# 3_CAN_CENR-50M_Flow_Relays_LEDs.net
KiCad netlist of a schematic drawn in Altium Designer
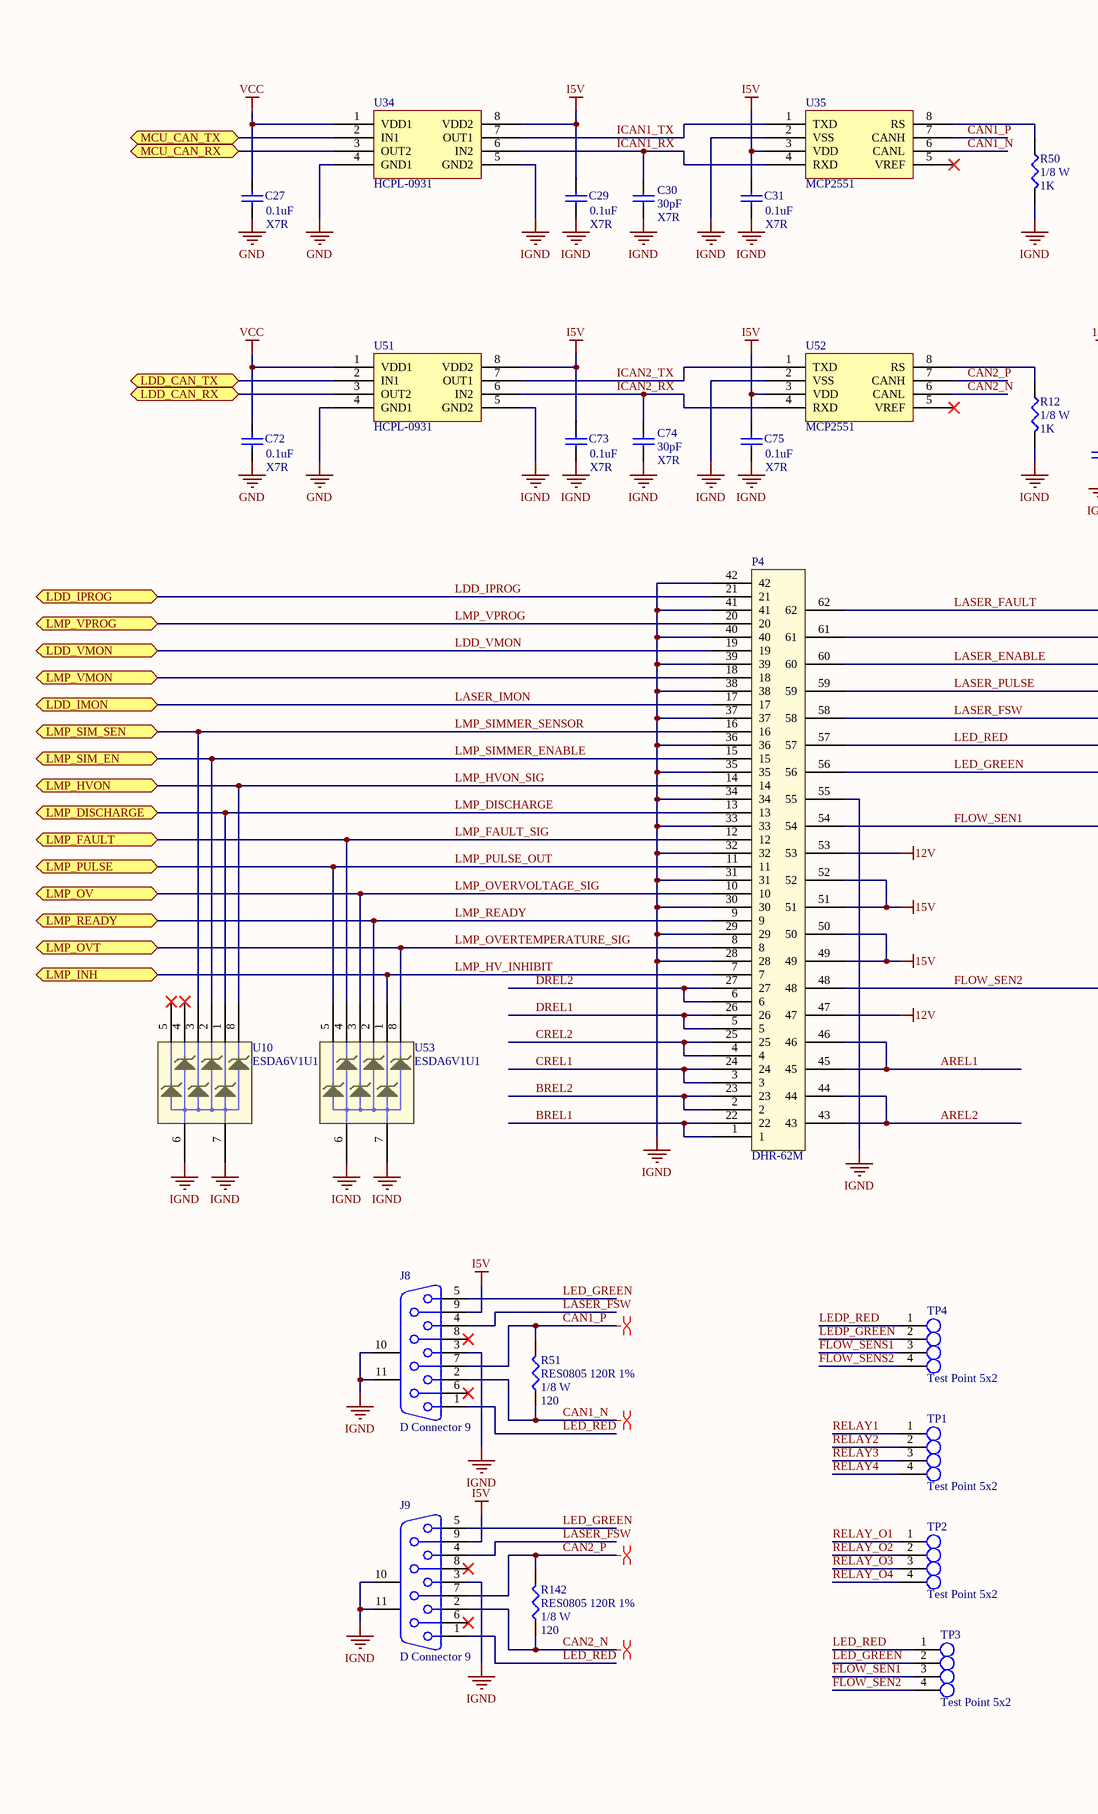
[diagram p0: [3] CAN, CENR-50M, Flow, Relays, LEDs.SchDoc, left]
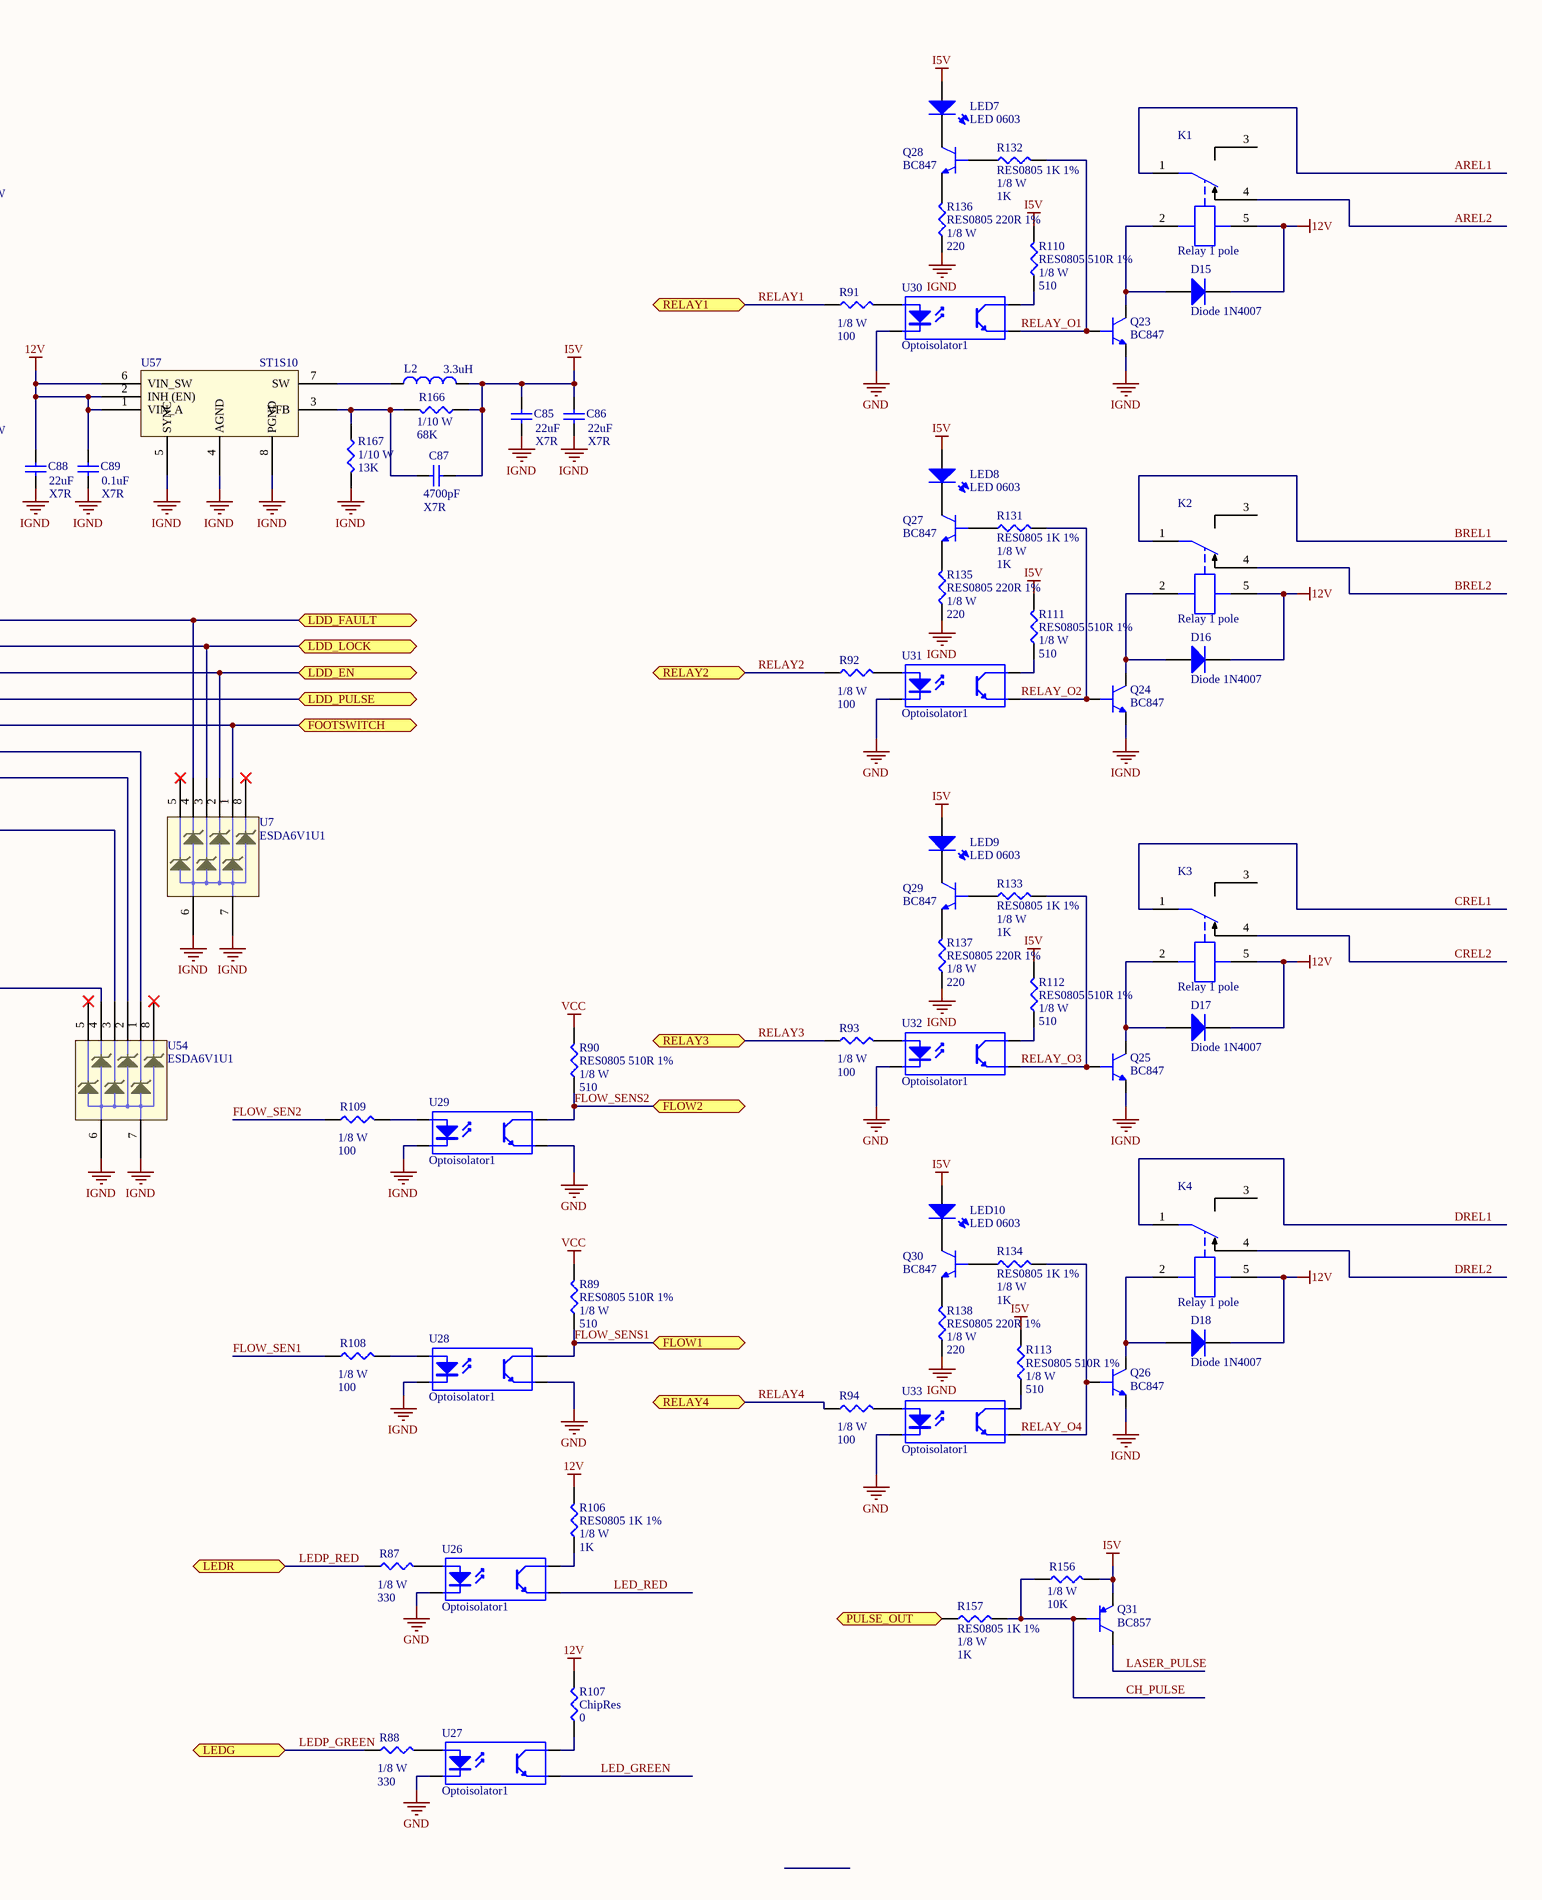
[diagram p1: [3] CAN, CENR-50M, Flow, Relays, LEDs.SchDoc, right]

(export (version "E")
  (design (tool "Eeschema 10.0.6"))
  (components
    (comp (ref "C27")
      (value "0.1uF")
      (footprint "CAP0805")
      (description "Surface-mount ceramic multilayer capacitor")
      (fields (field (name "VOLTAGE") "50V") (field (name "TOLERANCE") "5%") (field (name "TYPE") "X7R"))
      (libsource (lib "Capacitors") (part "CAP0805 0.1uF X7R"))
    )
    (comp (ref "C29")
      (value "0.1uF")
      (footprint "CAP0805")
      (description "Surface-mount ceramic multilayer capacitor")
      (fields (field (name "VOLTAGE") "50V") (field (name "TOLERANCE") "5%") (field (name "TYPE") "X7R"))
      (libsource (lib "Capacitors") (part "CAP0805 0.1uF X7R"))
    )
    (comp (ref "C30")
      (value "30pF")
      (footprint "CAP0805")
      (description "Surface-mount ceramic multilayer capacitor")
      (fields (field (name "VOLTAGE") "50V") (field (name "TOLERANCE") "5%") (field (name "TYPE") "X7R"))
      (libsource (lib "Capacitors") (part "CAP0805 30pF X7R"))
    )
    (comp (ref "C31")
      (value "0.1uF")
      (footprint "CAP0805")
      (description "Surface-mount ceramic multilayer capacitor")
      (fields (field (name "VOLTAGE") "50V") (field (name "TOLERANCE") "5%") (field (name "TYPE") "X7R"))
      (libsource (lib "Capacitors") (part "CAP0805 0.1uF X7R"))
    )
    (comp (ref "C72")
      (value "0.1uF")
      (footprint "CAP0805")
      (description "Surface-mount ceramic multilayer capacitor")
      (fields (field (name "VOLTAGE") "50V") (field (name "TOLERANCE") "5%") (field (name "TYPE") "X7R"))
      (libsource (lib "Capacitors") (part "CAP0805 0.1uF X7R"))
    )
    (comp (ref "C73")
      (value "0.1uF")
      (footprint "CAP0805")
      (description "Surface-mount ceramic multilayer capacitor")
      (fields (field (name "VOLTAGE") "50V") (field (name "TOLERANCE") "5%") (field (name "TYPE") "X7R"))
      (libsource (lib "Capacitors") (part "CAP0805 0.1uF X7R"))
    )
    (comp (ref "C74")
      (value "30pF")
      (footprint "CAP0805")
      (description "Surface-mount ceramic multilayer capacitor")
      (fields (field (name "VOLTAGE") "50V") (field (name "TOLERANCE") "5%") (field (name "TYPE") "X7R"))
      (libsource (lib "Capacitors") (part "CAP0805 30pF X7R"))
    )
    (comp (ref "C75")
      (value "0.1uF")
      (footprint "CAP0805")
      (description "Surface-mount ceramic multilayer capacitor")
      (fields (field (name "VOLTAGE") "50V") (field (name "TOLERANCE") "5%") (field (name "TYPE") "X7R"))
      (libsource (lib "Capacitors") (part "CAP0805 0.1uF X7R"))
    )
    (comp (ref "C85")
      (value "22uF")
      (footprint "CAP1210")
      (description "Surface-mount ceramic multilayer capacitor")
      (fields (field (name "VOLTAGE") "25V") (field (name "TOLERANCE") "10%") (field (name "TYPE") "X7R"))
      (libsource (lib "Capacitors") (part "ChipCap 22uF X7R"))
    )
    (comp (ref "C86")
      (value "22uF")
      (footprint "CAP1210")
      (description "Surface-mount ceramic multilayer capacitor")
      (fields (field (name "VOLTAGE") "25V") (field (name "TOLERANCE") "10%") (field (name "TYPE") "X7R"))
      (libsource (lib "Capacitors") (part "ChipCap 22uF X7R"))
    )
    (comp (ref "C87")
      (value "4700pF")
      (footprint "CAP0603")
      (description "Surface-mount ceramic multilayer capacitor")
      (fields (field (name "VOLTAGE") "16V") (field (name "TOLERANCE") "10%") (field (name "TYPE") "X7R"))
      (libsource (lib "Capacitors") (part "ChipCap 4700 X7R"))
    )
    (comp (ref "C88")
      (value "22uF")
      (footprint "CAP1210")
      (description "Surface-mount ceramic multilayer capacitor")
      (fields (field (name "VOLTAGE") "25V") (field (name "TOLERANCE") "10%") (field (name "TYPE") "X7R"))
      (libsource (lib "Capacitors") (part "ChipCap 22uF X7R"))
    )
    (comp (ref "C89")
      (value "0.1uF")
      (footprint "CAP0603")
      (description "Surface-mount ceramic multilayer capacitor")
      (fields (field (name "VOLTAGE") "100V") (field (name "TOLERANCE") "10%") (field (name "TYPE") "X7R"))
      (libsource (lib "Capacitors") (part "ChipCap 0.1uF X7R"))
    )
    (comp (ref "D15")
      (value "Diode 1N4007")
      (footprint "DO-41")
      (description "1 Amp General Purpose Rectifier")
      (fields (field (name "MANUFACTURER PART NUMBER") "1N4007") (field (name "PUBLISHER") "Altium Limited"))
      (libsource (lib "Miscellaneous Devices") (part "Diode 1N4007"))
    )
    (comp (ref "D16")
      (value "Diode 1N4007")
      (footprint "DO-41")
      (description "1 Amp General Purpose Rectifier")
      (fields (field (name "MANUFACTURER PART NUMBER") "1N4007") (field (name "PUBLISHER") "Altium Limited"))
      (libsource (lib "Miscellaneous Devices") (part "Diode 1N4007"))
    )
    (comp (ref "D17")
      (value "Diode 1N4007")
      (footprint "DO-41")
      (description "1 Amp General Purpose Rectifier")
      (fields (field (name "MANUFACTURER PART NUMBER") "1N4007") (field (name "PUBLISHER") "Altium Limited"))
      (libsource (lib "Miscellaneous Devices") (part "Diode 1N4007"))
    )
    (comp (ref "D18")
      (value "Diode 1N4007")
      (footprint "DO-41")
      (description "1 Amp General Purpose Rectifier")
      (fields (field (name "MANUFACTURER PART NUMBER") "1N4007") (field (name "PUBLISHER") "Altium Limited"))
      (libsource (lib "Miscellaneous Devices") (part "Diode 1N4007"))
    )
    (comp (ref "J8")
      (value "D Connector 9")
      (footprint "DSUB1.385-2H9F")
      (description "Receptacle Assembly, 9 Position, Right Angle")
      (fields
        (field (name "MANUFACTURER PART NUMBER") "DRB-9FA")
        (field (name "MANUFACTURER") "CONNFLY")
        (field (name "PUBLISHER") "Altium Limited")
      )
      (libsource (lib "Connectors") (part "D Connector 9"))
    )
    (comp (ref "J9")
      (value "D Connector 9")
      (footprint "DSUB1.385-2H9F")
      (description "Receptacle Assembly, 9 Position, Right Angle")
      (fields
        (field (name "MANUFACTURER PART NUMBER") "DRB-9FA")
        (field (name "MANUFACTURER") "CONNFLY")
        (field (name "PUBLISHER") "Altium Limited")
      )
      (libsource (lib "Connectors") (part "D Connector 9"))
    )
    (comp (ref "K1")
      (value "Relay 1 pole")
      (footprint "G5LA")
      (description "Relay G5LE 10A Single Pole")
      (libsource (lib "OMRON Relay") (part "Relay G5LE"))
    )
    (comp (ref "K2")
      (value "Relay 1 pole")
      (footprint "G5LA")
      (description "Relay G5LE 10A Single Pole")
      (libsource (lib "OMRON Relay") (part "Relay G5LE"))
    )
    (comp (ref "K3")
      (value "Relay 1 pole")
      (footprint "G5LA")
      (description "Relay G5LE 10A Single Pole")
      (libsource (lib "OMRON Relay") (part "Relay G5LE"))
    )
    (comp (ref "K4")
      (value "Relay 1 pole")
      (footprint "G5LA")
      (description "Relay G5LE 10A Single Pole")
      (libsource (lib "OMRON Relay") (part "Relay G5LE"))
    )
    (comp (ref "L2")
      (value "3.3uH")
      (footprint "SDR0403")
      (description "Inductance")
      (libsource (lib "Common Devices") (part "ChipInductance"))
    )
    (comp (ref "LED7") (value "LED 0603") (footprint "LED 0603") (libsource (lib "LEDs") (part "LED0603")))
    (comp (ref "LED8") (value "LED 0603") (footprint "LED 0603") (libsource (lib "LEDs") (part "LED0603")))
    (comp (ref "LED9") (value "LED 0603") (footprint "LED 0603") (libsource (lib "LEDs") (part "LED0603")))
    (comp (ref "LED10") (value "LED 0603") (footprint "LED 0603") (libsource (lib "LEDs") (part "LED0603")))
    (comp (ref "P4")
      (value "DHR-62M")
      (footprint "DHR-62M")
      (description "Dsub 62 Mail")
      (fields
        (field (name "MANUFACTURER PART NUMBER") "DS1038-62MBNSIA74")
        (field (name "MANUFACTURER") "CONNFLY")
      )
      (libsource (lib "Connectors") (part "DHR-62M"))
    )
    (comp (ref "Q23")
      (value "BC847")
      (footprint "SOT23")
      (description "NPN transistor")
      (fields (field (name "MANUFACTURER") "ONS") (field (name "MANUFACTURER PART NUMBER") "BC847BLT1G"))
      (libsource (lib "BJT") (part "BC847"))
    )
    (comp (ref "Q24")
      (value "BC847")
      (footprint "SOT23")
      (description "NPN transistor")
      (fields (field (name "MANUFACTURER") "ONS") (field (name "MANUFACTURER PART NUMBER") "BC847BLT1G"))
      (libsource (lib "BJT") (part "BC847"))
    )
    (comp (ref "Q25")
      (value "BC847")
      (footprint "SOT23")
      (description "NPN transistor")
      (fields (field (name "MANUFACTURER") "ONS") (field (name "MANUFACTURER PART NUMBER") "BC847BLT1G"))
      (libsource (lib "BJT") (part "BC847"))
    )
    (comp (ref "Q26")
      (value "BC847")
      (footprint "SOT23")
      (description "NPN transistor")
      (fields (field (name "MANUFACTURER") "ONS") (field (name "MANUFACTURER PART NUMBER") "BC847BLT1G"))
      (libsource (lib "BJT") (part "BC847"))
    )
    (comp (ref "Q27")
      (value "BC847")
      (footprint "SOT23")
      (description "NPN transistor")
      (fields (field (name "MANUFACTURER") "ONS") (field (name "MANUFACTURER PART NUMBER") "BC847BLT1G"))
      (libsource (lib "BJT") (part "BC847"))
    )
    (comp (ref "Q28")
      (value "BC847")
      (footprint "SOT23")
      (description "NPN transistor")
      (fields (field (name "MANUFACTURER") "ONS") (field (name "MANUFACTURER PART NUMBER") "BC847BLT1G"))
      (libsource (lib "BJT") (part "BC847"))
    )
    (comp (ref "Q29")
      (value "BC847")
      (footprint "SOT23")
      (description "NPN transistor")
      (fields (field (name "MANUFACTURER") "ONS") (field (name "MANUFACTURER PART NUMBER") "BC847BLT1G"))
      (libsource (lib "BJT") (part "BC847"))
    )
    (comp (ref "Q30")
      (value "BC847")
      (footprint "SOT23")
      (description "NPN transistor")
      (fields (field (name "MANUFACTURER") "ONS") (field (name "MANUFACTURER PART NUMBER") "BC847BLT1G"))
      (libsource (lib "BJT") (part "BC847"))
    )
    (comp (ref "Q31")
      (value "BC857")
      (footprint "SOT23")
      (description "PNP Transistor")
      (fields (field (name "MANUFACTURER") "NXP") (field (name "MANUFACTURER PART NUMBER") "BC857A.215"))
      (libsource (lib "BJT") (part "BC857"))
    )
    (comp (ref "R12")
      (value "1K")
      (footprint "RES0805")
      (description "Think Film Chip resistor")
      (fields
        (field (name "TOLERANCE") "1%")
        (field (name "MANUFACTURER PART NUMBER") "RC0805FR-071KL")
        (field (name "RATING") "1/8 W")
      )
      (libsource (lib "Resistors") (part "RES0805 1K 1%"))
    )
    (comp (ref "R50")
      (value "1K")
      (footprint "RES0805")
      (description "Think Film Chip resistor")
      (fields
        (field (name "TOLERANCE") "1%")
        (field (name "MANUFACTURER PART NUMBER") "RC0805FR-071KL")
        (field (name "RATING") "1/8 W")
      )
      (libsource (lib "Resistors") (part "RES0805 1K 1%"))
    )
    (comp (ref "R51")
      (value "RES0805 120R 1%")
      (footprint "RES0805")
      (description "Think Film Chip resistor")
      (fields
        (field (name "TOLERANCE") "1%")
        (field (name "MANUFACTURER PART NUMBER") "RC0805FR-07120RL")
        (field (name "RATING") "1/8 W")
        (field (name "ALTIUM_VALUE") "120")
      )
      (libsource (lib "Resistors") (part "RES0805 120R 1%"))
    )
    (comp (ref "R87")
      (value "330")
      (footprint "RES0805")
      (description "Think Film Chip resistor")
      (fields
        (field (name "TOLERANCE") "1%")
        (field (name "MANUFACTURER PART NUMBER") "RC0805FR-07330RL")
        (field (name "RATING") "1/8 W")
      )
      (libsource (lib "Resistors") (part "RES0805 330R 1%"))
    )
    (comp (ref "R88")
      (value "330")
      (footprint "RES0805")
      (description "Think Film Chip resistor")
      (fields
        (field (name "TOLERANCE") "1%")
        (field (name "MANUFACTURER PART NUMBER") "RC0805FR-07330RL")
        (field (name "RATING") "1/8 W")
      )
      (libsource (lib "Resistors") (part "RES0805 330R 1%"))
    )
    (comp (ref "R89")
      (value "RES0805 510R 1%")
      (footprint "RES0805")
      (description "Think Film Chip resistor")
      (fields
        (field (name "TOLERANCE") "1%")
        (field (name "MANUFACTURER PART NUMBER") "RC0805FR-07510RL")
        (field (name "RATING") "1/8 W")
        (field (name "ALTIUM_VALUE") "510")
      )
      (libsource (lib "Resistors") (part "RES0805 510R 1%"))
    )
    (comp (ref "R90")
      (value "RES0805 510R 1%")
      (footprint "RES0805")
      (description "Think Film Chip resistor")
      (fields
        (field (name "TOLERANCE") "1%")
        (field (name "MANUFACTURER PART NUMBER") "RC0805FR-07510RL")
        (field (name "RATING") "1/8 W")
        (field (name "ALTIUM_VALUE") "510")
      )
      (libsource (lib "Resistors") (part "RES0805 510R 1%"))
    )
    (comp (ref "R91")
      (value "100")
      (footprint "RES0805")
      (description "Think Film Chip resistor")
      (fields
        (field (name "TOLERANCE") "1%")
        (field (name "MANUFACTURER PART NUMBER") "RC0805FR-07100RL")
        (field (name "RATING") "1/8 W")
      )
      (libsource (lib "Resistors") (part "RES0805 100R 1%"))
    )
    (comp (ref "R92")
      (value "100")
      (footprint "RES0805")
      (description "Think Film Chip resistor")
      (fields
        (field (name "TOLERANCE") "1%")
        (field (name "MANUFACTURER PART NUMBER") "RC0805FR-07100RL")
        (field (name "RATING") "1/8 W")
      )
      (libsource (lib "Resistors") (part "RES0805 100R 1%"))
    )
    (comp (ref "R93")
      (value "100")
      (footprint "RES0805")
      (description "Think Film Chip resistor")
      (fields
        (field (name "TOLERANCE") "1%")
        (field (name "MANUFACTURER PART NUMBER") "RC0805FR-07100RL")
        (field (name "RATING") "1/8 W")
      )
      (libsource (lib "Resistors") (part "RES0805 100R 1%"))
    )
    (comp (ref "R94")
      (value "100")
      (footprint "RES0805")
      (description "Think Film Chip resistor")
      (fields
        (field (name "TOLERANCE") "1%")
        (field (name "MANUFACTURER PART NUMBER") "RC0805FR-07100RL")
        (field (name "RATING") "1/8 W")
      )
      (libsource (lib "Resistors") (part "RES0805 100R 1%"))
    )
    (comp (ref "R106")
      (value "RES0805 1K 1%")
      (footprint "RES0805")
      (description "Think Film Chip resistor")
      (fields
        (field (name "TOLERANCE") "1%")
        (field (name "MANUFACTURER PART NUMBER") "RC0805FR-071KL")
        (field (name "RATING") "1/8 W")
        (field (name "ALTIUM_VALUE") "1K")
      )
      (libsource (lib "Resistors") (part "RES0805 1K 1%"))
    )
    (comp (ref "R107")
      (value "ChipRes")
      (footprint "RES0805")
      (description "Chip resistor")
      (fields (field (name "ALTIUM_VALUE") "0"))
      (libsource (lib "Common Devices") (part "ChipRes"))
    )
    (comp (ref "R108")
      (value "100")
      (footprint "RES0805")
      (description "Think Film Chip resistor")
      (fields
        (field (name "TOLERANCE") "1%")
        (field (name "MANUFACTURER PART NUMBER") "RC0805FR-07100RL")
        (field (name "RATING") "1/8 W")
      )
      (libsource (lib "Resistors") (part "RES0805 100R 1%"))
    )
    (comp (ref "R109")
      (value "100")
      (footprint "RES0805")
      (description "Think Film Chip resistor")
      (fields
        (field (name "TOLERANCE") "1%")
        (field (name "MANUFACTURER PART NUMBER") "RC0805FR-07100RL")
        (field (name "RATING") "1/8 W")
      )
      (libsource (lib "Resistors") (part "RES0805 100R 1%"))
    )
    (comp (ref "R110")
      (value "RES0805 510R 1%")
      (footprint "RES0805")
      (description "Think Film Chip resistor")
      (fields
        (field (name "TOLERANCE") "1%")
        (field (name "MANUFACTURER PART NUMBER") "RC0805FR-07510RL")
        (field (name "RATING") "1/8 W")
        (field (name "ALTIUM_VALUE") "510")
      )
      (libsource (lib "Resistors") (part "RES0805 510R 1%"))
    )
    (comp (ref "R111")
      (value "RES0805 510R 1%")
      (footprint "RES0805")
      (description "Think Film Chip resistor")
      (fields
        (field (name "TOLERANCE") "1%")
        (field (name "MANUFACTURER PART NUMBER") "RC0805FR-07510RL")
        (field (name "RATING") "1/8 W")
        (field (name "ALTIUM_VALUE") "510")
      )
      (libsource (lib "Resistors") (part "RES0805 510R 1%"))
    )
    (comp (ref "R112")
      (value "RES0805 510R 1%")
      (footprint "RES0805")
      (description "Think Film Chip resistor")
      (fields
        (field (name "TOLERANCE") "1%")
        (field (name "MANUFACTURER PART NUMBER") "RC0805FR-07510RL")
        (field (name "RATING") "1/8 W")
        (field (name "ALTIUM_VALUE") "510")
      )
      (libsource (lib "Resistors") (part "RES0805 510R 1%"))
    )
    (comp (ref "R113")
      (value "RES0805 510R 1%")
      (footprint "RES0805")
      (description "Think Film Chip resistor")
      (fields
        (field (name "TOLERANCE") "1%")
        (field (name "MANUFACTURER PART NUMBER") "RC0805FR-07510RL")
        (field (name "RATING") "1/8 W")
        (field (name "ALTIUM_VALUE") "510")
      )
      (libsource (lib "Resistors") (part "RES0805 510R 1%"))
    )
    (comp (ref "R131")
      (value "RES0805 1K 1%")
      (footprint "RES0805")
      (description "Think Film Chip resistor")
      (fields
        (field (name "TOLERANCE") "1%")
        (field (name "MANUFACTURER PART NUMBER") "RC0805FR-071KL")
        (field (name "RATING") "1/8 W")
        (field (name "ALTIUM_VALUE") "1K")
      )
      (libsource (lib "Resistors") (part "RES0805 1K 1%"))
    )
    (comp (ref "R132")
      (value "RES0805 1K 1%")
      (footprint "RES0805")
      (description "Think Film Chip resistor")
      (fields
        (field (name "TOLERANCE") "1%")
        (field (name "MANUFACTURER PART NUMBER") "RC0805FR-071KL")
        (field (name "RATING") "1/8 W")
        (field (name "ALTIUM_VALUE") "1K")
      )
      (libsource (lib "Resistors") (part "RES0805 1K 1%"))
    )
    (comp (ref "R133")
      (value "RES0805 1K 1%")
      (footprint "RES0805")
      (description "Think Film Chip resistor")
      (fields
        (field (name "TOLERANCE") "1%")
        (field (name "MANUFACTURER PART NUMBER") "RC0805FR-071KL")
        (field (name "RATING") "1/8 W")
        (field (name "ALTIUM_VALUE") "1K")
      )
      (libsource (lib "Resistors") (part "RES0805 1K 1%"))
    )
    (comp (ref "R134")
      (value "RES0805 1K 1%")
      (footprint "RES0805")
      (description "Think Film Chip resistor")
      (fields
        (field (name "TOLERANCE") "1%")
        (field (name "MANUFACTURER PART NUMBER") "RC0805FR-071KL")
        (field (name "RATING") "1/8 W")
        (field (name "ALTIUM_VALUE") "1K")
      )
      (libsource (lib "Resistors") (part "RES0805 1K 1%"))
    )
    (comp (ref "R135")
      (value "RES0805 220R 1%")
      (footprint "RES0805")
      (description "Think Film Chip resistor")
      (fields
        (field (name "TOLERANCE") "1%")
        (field (name "MANUFACTURER PART NUMBER") "RC0805JR-07220R")
        (field (name "RATING") "1/8 W")
        (field (name "ALTIUM_VALUE") "220")
      )
      (libsource (lib "Resistors") (part "RES0805 220R 1%"))
    )
    (comp (ref "R136")
      (value "RES0805 220R 1%")
      (footprint "RES0805")
      (description "Think Film Chip resistor")
      (fields
        (field (name "TOLERANCE") "1%")
        (field (name "MANUFACTURER PART NUMBER") "RC0805JR-07220R")
        (field (name "RATING") "1/8 W")
        (field (name "ALTIUM_VALUE") "220")
      )
      (libsource (lib "Resistors") (part "RES0805 220R 1%"))
    )
    (comp (ref "R137")
      (value "RES0805 220R 1%")
      (footprint "RES0805")
      (description "Think Film Chip resistor")
      (fields
        (field (name "TOLERANCE") "1%")
        (field (name "MANUFACTURER PART NUMBER") "RC0805JR-07220R")
        (field (name "RATING") "1/8 W")
        (field (name "ALTIUM_VALUE") "220")
      )
      (libsource (lib "Resistors") (part "RES0805 220R 1%"))
    )
    (comp (ref "R138")
      (value "RES0805 220R 1%")
      (footprint "RES0805")
      (description "Think Film Chip resistor")
      (fields
        (field (name "TOLERANCE") "1%")
        (field (name "MANUFACTURER PART NUMBER") "RC0805JR-07220R")
        (field (name "RATING") "1/8 W")
        (field (name "ALTIUM_VALUE") "220")
      )
      (libsource (lib "Resistors") (part "RES0805 220R 1%"))
    )
    (comp (ref "R142")
      (value "RES0805 120R 1%")
      (footprint "RES0805")
      (description "Think Film Chip resistor")
      (fields
        (field (name "TOLERANCE") "1%")
        (field (name "MANUFACTURER PART NUMBER") "RC0805FR-07120RL")
        (field (name "RATING") "1/8 W")
        (field (name "ALTIUM_VALUE") "120")
      )
      (libsource (lib "Resistors") (part "RES0805 120R 1%"))
    )
    (comp (ref "R156")
      (value "10K")
      (footprint "RES0805")
      (description "Think Film Chip resistor")
      (fields
        (field (name "TOLERANCE") "1%")
        (field (name "MANUFACTURER PART NUMBER") "RC0805FR-0710KL")
        (field (name "RATING") "1/8 W")
      )
      (libsource (lib "Resistors") (part "RES0805 10K 1%"))
    )
    (comp (ref "R157")
      (value "RES0805 1K 1%")
      (footprint "RES0805")
      (description "Think Film Chip resistor")
      (fields
        (field (name "TOLERANCE") "1%")
        (field (name "MANUFACTURER PART NUMBER") "RC0805FR-071KL")
        (field (name "RATING") "1/8 W")
        (field (name "ALTIUM_VALUE") "1K")
      )
      (libsource (lib "Resistors") (part "RES0805 1K 1%"))
    )
    (comp (ref "R166")
      (value "68K")
      (footprint "RES0603")
      (description "Think Film Chip resistor")
      (fields
        (field (name "TOLERANCE") "1%")
        (field (name "RATING") "1/10 W")
        (field (name "Comment") "ChipRes 68K 1%")
      )
      (libsource (lib "Resistors") (part "ChipRes 1K5 1%"))
    )
    (comp (ref "R167")
      (value "13K")
      (footprint "RES0603")
      (description "Think Film Chip resistor")
      (fields
        (field (name "TOLERANCE") "1%")
        (field (name "RATING") "1/10 W")
        (field (name "Comment") "ChipRes 13K 1%")
      )
      (libsource (lib "Resistors") (part "ChipRes 1K5 1%"))
    )
    (comp (ref "TP1")
      (value "Test Point 5x2")
      (footprint "PG-1.5-13.5-4P-2.54PH")
      (libsource (lib "Connectors") (part "PG-1.5-13.5-4P-2.54PH"))
    )
    (comp (ref "TP2")
      (value "Test Point 5x2")
      (footprint "PG-1.5-13.5-4P-2.54PH")
      (libsource (lib "Connectors") (part "PG-1.5-13.5-4P-2.54PH"))
    )
    (comp (ref "TP3")
      (value "Test Point 5x2")
      (footprint "PG-1.5-13.5-4P-2.54PH")
      (libsource (lib "Connectors") (part "PG-1.5-13.5-4P-2.54PH"))
    )
    (comp (ref "TP4")
      (value "Test Point 5x2")
      (footprint "PG-1.5-13.5-4P-2.54PH")
      (libsource (lib "Connectors") (part "PG-1.5-13.5-4P-2.54PH"))
    )
    (comp (ref "U7")
      (value "ESDA6V1U1")
      (footprint "Protection:SOP8")
      (description "Transil Array for ESD protection")
      (libsource (lib "Protection") (part "ESDA6V1U1"))
    )
    (comp (ref "U10")
      (value "ESDA6V1U1")
      (footprint "Protection:SOP8")
      (description "Transil Array for ESD protection")
      (libsource (lib "Protection") (part "ESDA6V1U1"))
    )
    (comp (ref "U26")
      (value "Optoisolator1")
      (footprint "DIP-4")
      (description "4-Pin Phototransistor Optocoupler")
      (fields (field (name "PUBLISHER") "Altium Limited"))
      (libsource (lib "Miscellaneous Devices") (part "Optoisolator1"))
    )
    (comp (ref "U27")
      (value "Optoisolator1")
      (footprint "DIP-4")
      (description "4-Pin Phototransistor Optocoupler")
      (fields (field (name "PUBLISHER") "Altium Limited"))
      (libsource (lib "Miscellaneous Devices") (part "Optoisolator1"))
    )
    (comp (ref "U28")
      (value "Optoisolator1")
      (footprint "DIP-4")
      (description "4-Pin Phototransistor Optocoupler")
      (fields (field (name "PUBLISHER") "Altium Limited"))
      (libsource (lib "Miscellaneous Devices") (part "Optoisolator1"))
    )
    (comp (ref "U29")
      (value "Optoisolator1")
      (footprint "DIP-4")
      (description "4-Pin Phototransistor Optocoupler")
      (fields (field (name "PUBLISHER") "Altium Limited"))
      (libsource (lib "Miscellaneous Devices") (part "Optoisolator1"))
    )
    (comp (ref "U30")
      (value "Optoisolator1")
      (footprint "DIP-4")
      (description "4-Pin Phototransistor Optocoupler")
      (fields (field (name "PUBLISHER") "Altium Limited"))
      (libsource (lib "Miscellaneous Devices") (part "Optoisolator1"))
    )
    (comp (ref "U31")
      (value "Optoisolator1")
      (footprint "DIP-4")
      (description "4-Pin Phototransistor Optocoupler")
      (fields (field (name "PUBLISHER") "Altium Limited"))
      (libsource (lib "Miscellaneous Devices") (part "Optoisolator1"))
    )
    (comp (ref "U32")
      (value "Optoisolator1")
      (footprint "DIP-4")
      (description "4-Pin Phototransistor Optocoupler")
      (fields (field (name "PUBLISHER") "Altium Limited"))
      (libsource (lib "Miscellaneous Devices") (part "Optoisolator1"))
    )
    (comp (ref "U33")
      (value "Optoisolator1")
      (footprint "DIP-4")
      (description "4-Pin Phototransistor Optocoupler")
      (fields (field (name "PUBLISHER") "Altium Limited"))
      (libsource (lib "Miscellaneous Devices") (part "Optoisolator1"))
    )
    (comp (ref "U34")
      (value "HCPL-0931")
      (footprint "SOIC8")
      (description "2-bit bi-direction optoisolated buffer")
      (libsource (lib "AVAGO bi-direction optoisolated buffer") (part "HCPL-0931-000E"))
    )
    (comp (ref "U35")
      (value "MCP2551")
      (footprint "SOIC8")
      (description "CAN Transceiver")
      (libsource (lib "Microchip CAN Transceiver") (part "MCP2551-I/SN"))
    )
    (comp (ref "U51")
      (value "HCPL-0931")
      (footprint "SOIC8")
      (description "2-bit bi-direction optoisolated buffer")
      (libsource (lib "AVAGO bi-direction optoisolated buffer") (part "HCPL-0931-000E"))
    )
    (comp (ref "U52")
      (value "MCP2551")
      (footprint "SOIC8")
      (description "CAN Transceiver")
      (libsource (lib "Microchip CAN Transceiver") (part "MCP2551-I/SN"))
    )
    (comp (ref "U53")
      (value "ESDA6V1U1")
      (footprint "Protection:SOP8")
      (description "Transil Array for ESD protection")
      (libsource (lib "Protection") (part "ESDA6V1U1"))
    )
    (comp (ref "U54")
      (value "ESDA6V1U1")
      (footprint "Protection:SOP8")
      (description "Transil Array for ESD protection")
      (libsource (lib "Protection") (part "ESDA6V1U1"))
    )
    (comp (ref "U57")
      (value "ST1S10")
      (footprint "SOIC8")
      (description "3 A, 900 kHz, monolithic synchronous step-down regulator IC")
      (fields (field (name "MANUFACTURER") "ST"))
      (libsource (lib "ST DC-DC") (part "ST1S10"))
    )
  )
  (nets
    (net (code "1") (name "/AREL1") (class "Default")
      (node (ref "K1") (pin "1") (pinfunction "1_1") (pintype "passive"))
      (node (ref "P4") (pin "45") (pinfunction "45_45") (pintype "passive"))
      (node (ref "P4") (pin "46") (pinfunction "46_46") (pintype "passive"))
    )
    (net (code "2") (name "/AREL2") (class "Default")
      (node (ref "K1") (pin "4") (pinfunction "4_4") (pintype "passive"))
      (node (ref "P4") (pin "43") (pinfunction "43_43") (pintype "passive"))
      (node (ref "P4") (pin "44") (pinfunction "44_44") (pintype "passive"))
    )
    (net (code "3") (name "/BREL1") (class "Default")
      (node (ref "K2") (pin "1") (pinfunction "1_1") (pintype "passive"))
      (node (ref "P4") (pin "1") (pinfunction "1_1") (pintype "passive"))
      (node (ref "P4") (pin "22") (pinfunction "22_22") (pintype "passive"))
    )
    (net (code "4") (name "/BREL2") (class "Default")
      (node (ref "K2") (pin "4") (pinfunction "4_4") (pintype "passive"))
      (node (ref "P4") (pin "2") (pinfunction "2_2") (pintype "passive"))
      (node (ref "P4") (pin "23") (pinfunction "23_23") (pintype "passive"))
    )
    (net (code "5") (name "/CAN1_N") (class "Default")
      (node (ref "J8") (pin "2") (pinfunction "2_2") (pintype "passive"))
      (node (ref "R51") (pin "1") (pintype "passive"))
      (node (ref "U35") (pin "6") (pinfunction "CANL_6") (pintype "passive"))
    )
    (net (code "6") (name "/CAN1_P") (class "Default")
      (node (ref "J8") (pin "7") (pinfunction "7_7") (pintype "passive"))
      (node (ref "R51") (pin "2") (pintype "passive"))
      (node (ref "U35") (pin "7") (pinfunction "CANH_7") (pintype "passive"))
    )
    (net (code "7") (name "/CAN2_N") (class "Default")
      (node (ref "J9") (pin "2") (pinfunction "2_2") (pintype "passive"))
      (node (ref "R142") (pin "1") (pintype "passive"))
      (node (ref "U52") (pin "6") (pinfunction "CANL_6") (pintype "passive"))
    )
    (net (code "8") (name "/CAN2_P") (class "Default")
      (node (ref "J9") (pin "7") (pinfunction "7_7") (pintype "passive"))
      (node (ref "R142") (pin "2") (pintype "passive"))
      (node (ref "U52") (pin "7") (pinfunction "CANH_7") (pintype "passive"))
    )
    (net (code "9") (name "/CH_PULSE") (class "Default")
      (node (ref "Q31") (pin "1") (pinfunction "1_1") (pintype "passive"))
      (node (ref "R156") (pin "1") (pintype "passive"))
      (node (ref "R157") (pin "2") (pintype "passive"))
    )
    (net (code "10") (name "/CREL1") (class "Default")
      (node (ref "K3") (pin "1") (pinfunction "1_1") (pintype "passive"))
      (node (ref "P4") (pin "24") (pinfunction "24_24") (pintype "passive"))
      (node (ref "P4") (pin "3") (pinfunction "3_3") (pintype "passive"))
    )
    (net (code "11") (name "/CREL2") (class "Default")
      (node (ref "K3") (pin "4") (pinfunction "4_4") (pintype "passive"))
      (node (ref "P4") (pin "25") (pinfunction "25_25") (pintype "passive"))
      (node (ref "P4") (pin "4") (pinfunction "4_4") (pintype "passive"))
    )
    (net (code "12") (name "/DREL1") (class "Default")
      (node (ref "K4") (pin "1") (pinfunction "1_1") (pintype "passive"))
      (node (ref "P4") (pin "26") (pinfunction "26_26") (pintype "passive"))
      (node (ref "P4") (pin "5") (pinfunction "5_5") (pintype "passive"))
    )
    (net (code "13") (name "/DREL2") (class "Default")
      (node (ref "K4") (pin "4") (pinfunction "4_4") (pintype "passive"))
      (node (ref "P4") (pin "27") (pinfunction "27_27") (pintype "passive"))
      (node (ref "P4") (pin "6") (pinfunction "6_6") (pintype "passive"))
    )
    (net (code "14") (name "/FLOW_SEN1") (class "Default")
      (node (ref "P4") (pin "54") (pinfunction "54_54") (pintype "passive"))
      (node (ref "R108") (pin "1") (pintype "passive"))
      (node (ref "TP3") (pin "3") (pinfunction "3_3") (pintype "passive"))
      (node (ref "U54") (pin "3") (pinfunction "3_3") (pintype "passive"))
    )
    (net (code "15") (name "/FLOW_SEN2") (class "Default")
      (node (ref "P4") (pin "48") (pinfunction "48_48") (pintype "passive"))
      (node (ref "R109") (pin "1") (pintype "passive"))
      (node (ref "TP3") (pin "4") (pinfunction "4_4") (pintype "passive"))
      (node (ref "U54") (pin "4") (pinfunction "4_4") (pintype "passive"))
    )
    (net (code "16") (name "/FLOW_SENS1") (class "Default")
      (node (ref "R89") (pin "1") (pintype "passive"))
      (node (ref "TP4") (pin "3") (pinfunction "3_3") (pintype "passive"))
      (node (ref "U28") (pin "4") (pinfunction "C_4") (pintype "passive"))
    )
    (net (code "17") (name "/FLOW_SENS2") (class "Default")
      (node (ref "R90") (pin "1") (pintype "passive"))
      (node (ref "TP4") (pin "4") (pinfunction "4_4") (pintype "passive"))
      (node (ref "U29") (pin "4") (pinfunction "C_4") (pintype "passive"))
    )
    (net (code "18") (name "/ICAN1_RX") (class "Default")
      (node (ref "C30") (pin "2") (pinfunction "2_2") (pintype "passive"))
      (node (ref "U34") (pin "6") (pinfunction "IN2_6") (pintype "passive"))
      (node (ref "U35") (pin "4") (pinfunction "RXD_4") (pintype "passive"))
    )
    (net (code "19") (name "/ICAN1_TX") (class "Default")
      (node (ref "U34") (pin "7") (pinfunction "OUT1_7") (pintype "passive"))
      (node (ref "U35") (pin "1") (pinfunction "TXD_1") (pintype "passive"))
    )
    (net (code "20") (name "/ICAN2_RX") (class "Default")
      (node (ref "C74") (pin "2") (pinfunction "2_2") (pintype "passive"))
      (node (ref "U51") (pin "6") (pinfunction "IN2_6") (pintype "passive"))
      (node (ref "U52") (pin "4") (pinfunction "RXD_4") (pintype "passive"))
    )
    (net (code "21") (name "/ICAN2_TX") (class "Default")
      (node (ref "U51") (pin "7") (pinfunction "OUT1_7") (pintype "passive"))
      (node (ref "U52") (pin "1") (pinfunction "TXD_1") (pintype "passive"))
    )
    (net (code "22") (name "/LASER_ENABLE") (class "Default")
      (node (ref "P4") (pin "60") (pinfunction "60_60") (pintype "passive"))
      (node (ref "U7") (pin "2") (pinfunction "2_2") (pintype "passive"))
    )
    (net (code "23") (name "/LASER_FAULT") (class "Default")
      (node (ref "P4") (pin "62") (pinfunction "62_62") (pintype "passive"))
      (node (ref "U7") (pin "4") (pinfunction "4_4") (pintype "passive"))
    )
    (net (code "24") (name "/LASER_FSW") (class "Default")
      (node (ref "J8") (pin "4") (pinfunction "4_4") (pintype "passive"))
      (node (ref "J9") (pin "4") (pinfunction "4_4") (pintype "passive"))
      (node (ref "P4") (pin "58") (pinfunction "58_58") (pintype "passive"))
      (node (ref "U7") (pin "1") (pinfunction "1_1") (pintype "passive"))
    )
    (net (code "25") (name "/LASER_IMON") (class "Default")
      (node (ref "P4") (pin "17") (pinfunction "17_17") (pintype "passive"))
    )
    (net (code "26") (name "/LASER_PULSE") (class "Default")
      (node (ref "P4") (pin "59") (pinfunction "59_59") (pintype "passive"))
      (node (ref "Q31") (pin "3") (pinfunction "3_3") (pintype "passive"))
    )
    (net (code "27") (name "/LDD_CAN_RX") (class "Default")
      (node (ref "U51") (pin "3") (pinfunction "OUT2_3") (pintype "passive"))
    )
    (net (code "28") (name "/LDD_CAN_TX") (class "Default")
      (node (ref "U51") (pin "2") (pinfunction "IN1_2") (pintype "passive"))
    )
    (net (code "29") (name "/LDD_IPROG") (class "Default")
      (node (ref "P4") (pin "21") (pinfunction "21_21") (pintype "passive"))
    )
    (net (code "30") (name "/LDD_LOCK") (class "Default")
      (node (ref "P4") (pin "61") (pinfunction "61_61") (pintype "passive"))
      (node (ref "U7") (pin "3") (pinfunction "3_3") (pintype "passive"))
    )
    (net (code "31") (name "/LDD_VMON") (class "Default")
      (node (ref "P4") (pin "19") (pinfunction "19_19") (pintype "passive"))
    )
    (net (code "32") (name "/LEDP_GREEN") (class "Default")
      (node (ref "R88") (pin "1") (pintype "passive"))
      (node (ref "TP4") (pin "2") (pinfunction "2_2") (pintype "passive"))
    )
    (net (code "33") (name "/LEDP_RED") (class "Default")
      (node (ref "R87") (pin "1") (pintype "passive"))
      (node (ref "TP4") (pin "1") (pinfunction "1_1") (pintype "passive"))
    )
    (net (code "34") (name "/LED_GREEN") (class "Default")
      (node (ref "J8") (pin "5") (pinfunction "5_5") (pintype "passive"))
      (node (ref "J9") (pin "5") (pinfunction "5_5") (pintype "passive"))
      (node (ref "P4") (pin "56") (pinfunction "56_56") (pintype "passive"))
      (node (ref "TP3") (pin "2") (pinfunction "2_2") (pintype "passive"))
      (node (ref "U27") (pin "3") (pinfunction "E_3") (pintype "passive"))
      (node (ref "U54") (pin "2") (pinfunction "2_2") (pintype "passive"))
    )
    (net (code "35") (name "/LED_RED") (class "Default")
      (node (ref "J8") (pin "1") (pinfunction "1_1") (pintype "passive"))
      (node (ref "J9") (pin "1") (pinfunction "1_1") (pintype "passive"))
      (node (ref "P4") (pin "57") (pinfunction "57_57") (pintype "passive"))
      (node (ref "TP3") (pin "1") (pinfunction "1_1") (pintype "passive"))
      (node (ref "U26") (pin "3") (pinfunction "E_3") (pintype "passive"))
      (node (ref "U54") (pin "1") (pinfunction "1_1") (pintype "passive"))
    )
    (net (code "36") (name "/LMP_DISCHARGE") (class "Default")
      (node (ref "P4") (pin "13") (pinfunction "13_13") (pintype "passive"))
      (node (ref "U10") (pin "1") (pinfunction "1_1") (pintype "passive"))
    )
    (net (code "37") (name "/LMP_FAULT_SIG") (class "Default")
      (node (ref "P4") (pin "12") (pinfunction "12_12") (pintype "passive"))
      (node (ref "U53") (pin "4") (pinfunction "4_4") (pintype "passive"))
    )
    (net (code "38") (name "/LMP_HVON_SIG") (class "Default")
      (node (ref "P4") (pin "14") (pinfunction "14_14") (pintype "passive"))
      (node (ref "U10") (pin "8") (pinfunction "8_8") (pintype "passive"))
    )
    (net (code "39") (name "/LMP_HV_INHIBIT") (class "Default")
      (node (ref "P4") (pin "7") (pinfunction "7_7") (pintype "passive"))
      (node (ref "U53") (pin "1") (pinfunction "1_1") (pintype "passive"))
    )
    (net (code "40") (name "/LMP_OVERTEMPERATURE_SIG") (class "Default")
      (node (ref "P4") (pin "8") (pinfunction "8_8") (pintype "passive"))
      (node (ref "U53") (pin "8") (pinfunction "8_8") (pintype "passive"))
    )
    (net (code "41") (name "/LMP_OVERVOLTAGE_SIG") (class "Default")
      (node (ref "P4") (pin "10") (pinfunction "10_10") (pintype "passive"))
      (node (ref "U53") (pin "3") (pinfunction "3_3") (pintype "passive"))
    )
    (net (code "42") (name "/LMP_PULSE_OUT") (class "Default")
      (node (ref "P4") (pin "11") (pinfunction "11_11") (pintype "passive"))
      (node (ref "U53") (pin "5") (pinfunction "5_5") (pintype "passive"))
    )
    (net (code "43") (name "/LMP_READY") (class "Default")
      (node (ref "P4") (pin "9") (pinfunction "9_9") (pintype "passive"))
      (node (ref "U53") (pin "2") (pinfunction "2_2") (pintype "passive"))
    )
    (net (code "44") (name "/LMP_SIMMER_ENABLE") (class "Default")
      (node (ref "P4") (pin "15") (pinfunction "15_15") (pintype "passive"))
      (node (ref "U10") (pin "2") (pinfunction "2_2") (pintype "passive"))
    )
    (net (code "45") (name "/LMP_SIMMER_SENSOR") (class "Default")
      (node (ref "P4") (pin "16") (pinfunction "16_16") (pintype "passive"))
      (node (ref "U10") (pin "3") (pinfunction "3_3") (pintype "passive"))
    )
    (net (code "46") (name "/LMP_VMON") (class "Default")
      (node (ref "P4") (pin "18") (pinfunction "18_18") (pintype "passive"))
    )
    (net (code "47") (name "/LMP_VPROG") (class "Default")
      (node (ref "P4") (pin "20") (pinfunction "20_20") (pintype "passive"))
    )
    (net (code "48") (name "/MCU_CAN_RX") (class "Default")
      (node (ref "U34") (pin "3") (pinfunction "OUT2_3") (pintype "passive"))
    )
    (net (code "49") (name "/MCU_CAN_TX") (class "Default")
      (node (ref "U34") (pin "2") (pinfunction "IN1_2") (pintype "passive"))
    )
    (net (code "50") (name "/PULSE_OUT") (class "Default") (node (ref "R157") (pin "1") (pintype "passive")))
    (net (code "51") (name "/RELAY1") (class "Default")
      (node (ref "R91") (pin "1") (pintype "passive"))
      (node (ref "TP1") (pin "1") (pinfunction "1_1") (pintype "passive"))
    )
    (net (code "52") (name "/RELAY2") (class "Default")
      (node (ref "R92") (pin "1") (pintype "passive"))
      (node (ref "TP1") (pin "2") (pinfunction "2_2") (pintype "passive"))
    )
    (net (code "53") (name "/RELAY3") (class "Default")
      (node (ref "R93") (pin "1") (pintype "passive"))
      (node (ref "TP1") (pin "3") (pinfunction "3_3") (pintype "passive"))
    )
    (net (code "54") (name "/RELAY4") (class "Default")
      (node (ref "R94") (pin "1") (pintype "passive"))
      (node (ref "TP1") (pin "4") (pinfunction "4_4") (pintype "passive"))
    )
    (net (code "55") (name "/RELAY_O1") (class "Default")
      (node (ref "Q23") (pin "1") (pinfunction "1_1") (pintype "passive"))
      (node (ref "R132") (pin "2") (pintype "passive"))
      (node (ref "TP2") (pin "1") (pinfunction "1_1") (pintype "passive"))
      (node (ref "U30") (pin "3") (pinfunction "E_3") (pintype "passive"))
    )
    (net (code "56") (name "/RELAY_O2") (class "Default")
      (node (ref "Q24") (pin "1") (pinfunction "1_1") (pintype "passive"))
      (node (ref "R131") (pin "2") (pintype "passive"))
      (node (ref "TP2") (pin "2") (pinfunction "2_2") (pintype "passive"))
      (node (ref "U31") (pin "3") (pinfunction "E_3") (pintype "passive"))
    )
    (net (code "57") (name "/RELAY_O3") (class "Default")
      (node (ref "Q25") (pin "1") (pinfunction "1_1") (pintype "passive"))
      (node (ref "R133") (pin "2") (pintype "passive"))
      (node (ref "TP2") (pin "3") (pinfunction "3_3") (pintype "passive"))
      (node (ref "U32") (pin "3") (pinfunction "E_3") (pintype "passive"))
    )
    (net (code "58") (name "/RELAY_O4") (class "Default")
      (node (ref "Q26") (pin "1") (pinfunction "1_1") (pintype "passive"))
      (node (ref "R134") (pin "2") (pintype "passive"))
      (node (ref "TP2") (pin "4") (pinfunction "4_4") (pintype "passive"))
      (node (ref "U33") (pin "3") (pinfunction "E_3") (pintype "passive"))
    )
    (net (code "59") (name "12V") (class "Default")
      (node (ref "C88") (pin "2") (pinfunction "2_2") (pintype "passive"))
      (node (ref "C89") (pin "2") (pinfunction "2_2") (pintype "passive"))
      (node (ref "D15") (pin "2") (pinfunction "K_2") (pintype "passive"))
      (node (ref "D16") (pin "2") (pinfunction "K_2") (pintype "passive"))
      (node (ref "D17") (pin "2") (pinfunction "K_2") (pintype "passive"))
      (node (ref "D18") (pin "2") (pinfunction "K_2") (pintype "passive"))
      (node (ref "K1") (pin "5") (pinfunction "5_5") (pintype "passive"))
      (node (ref "K2") (pin "5") (pinfunction "5_5") (pintype "passive"))
      (node (ref "K3") (pin "5") (pinfunction "5_5") (pintype "passive"))
      (node (ref "K4") (pin "5") (pinfunction "5_5") (pintype "passive"))
      (node (ref "P4") (pin "47") (pinfunction "47_47") (pintype "passive"))
      (node (ref "P4") (pin "53") (pinfunction "53_53") (pintype "passive"))
      (node (ref "R106") (pin "2") (pintype "passive"))
      (node (ref "R107") (pin "2") (pintype "passive"))
      (node (ref "U57") (pin "1") (pinfunction "VIN_A_1") (pintype "passive"))
      (node (ref "U57") (pin "2") (pinfunction "INH_(EN)_2") (pintype "passive"))
      (node (ref "U57") (pin "6") (pinfunction "VIN_SW_6") (pintype "passive"))
    )
    (net (code "60") (name "15V") (class "Default")
      (node (ref "P4") (pin "49") (pinfunction "49_49") (pintype "passive"))
      (node (ref "P4") (pin "50") (pinfunction "50_50") (pintype "passive"))
      (node (ref "P4") (pin "51") (pinfunction "51_51") (pintype "passive"))
      (node (ref "P4") (pin "52") (pinfunction "52_52") (pintype "passive"))
    )
    (net (code "61") (name "GND") (class "Default")
      (node (ref "C27") (pin "1") (pinfunction "1_1") (pintype "passive"))
      (node (ref "C72") (pin "1") (pinfunction "1_1") (pintype "passive"))
      (node (ref "U26") (pin "2") (pinfunction "K_2") (pintype "passive"))
      (node (ref "U27") (pin "2") (pinfunction "K_2") (pintype "passive"))
      (node (ref "U28") (pin "3") (pinfunction "E_3") (pintype "passive"))
      (node (ref "U29") (pin "3") (pinfunction "E_3") (pintype "passive"))
      (node (ref "U30") (pin "2") (pinfunction "K_2") (pintype "passive"))
      (node (ref "U31") (pin "2") (pinfunction "K_2") (pintype "passive"))
      (node (ref "U32") (pin "2") (pinfunction "K_2") (pintype "passive"))
      (node (ref "U33") (pin "2") (pinfunction "K_2") (pintype "passive"))
      (node (ref "U34") (pin "4") (pinfunction "GND1_4") (pintype "passive"))
      (node (ref "U51") (pin "4") (pinfunction "GND1_4") (pintype "passive"))
    )
    (net (code "62") (name "I5V") (class "Default")
      (node (ref "C29") (pin "2") (pinfunction "2_2") (pintype "passive"))
      (node (ref "C31") (pin "2") (pinfunction "2_2") (pintype "passive"))
      (node (ref "C73") (pin "2") (pinfunction "2_2") (pintype "passive"))
      (node (ref "C75") (pin "2") (pinfunction "2_2") (pintype "passive"))
      (node (ref "C85") (pin "2") (pinfunction "2_2") (pintype "passive"))
      (node (ref "C86") (pin "2") (pinfunction "2_2") (pintype "passive"))
      (node (ref "C87") (pin "2") (pinfunction "2_2") (pintype "passive"))
      (node (ref "J8") (pin "9") (pinfunction "9_9") (pintype "passive"))
      (node (ref "J9") (pin "9") (pinfunction "9_9") (pintype "passive"))
      (node (ref "L2") (pin "1") (pintype "passive"))
      (node (ref "LED10") (pin "2") (pinfunction "2_2") (pintype "passive"))
      (node (ref "LED7") (pin "2") (pinfunction "2_2") (pintype "passive"))
      (node (ref "LED8") (pin "2") (pinfunction "2_2") (pintype "passive"))
      (node (ref "LED9") (pin "2") (pinfunction "2_2") (pintype "passive"))
      (node (ref "Q31") (pin "2") (pinfunction "2_2") (pintype "passive"))
      (node (ref "R110") (pin "2") (pintype "passive"))
      (node (ref "R111") (pin "2") (pintype "passive"))
      (node (ref "R112") (pin "2") (pintype "passive"))
      (node (ref "R113") (pin "2") (pintype "passive"))
      (node (ref "R156") (pin "2") (pintype "passive"))
      (node (ref "R166") (pin "1") (pintype "passive"))
      (node (ref "U34") (pin "8") (pinfunction "VDD2_8") (pintype "passive"))
      (node (ref "U35") (pin "3") (pinfunction "VDD_3") (pintype "passive"))
      (node (ref "U51") (pin "8") (pinfunction "VDD2_8") (pintype "passive"))
      (node (ref "U52") (pin "3") (pinfunction "VDD_3") (pintype "passive"))
    )
    (net (code "63") (name "IGND") (class "Default")
      (node (ref "C29") (pin "1") (pinfunction "1_1") (pintype "passive"))
      (node (ref "C30") (pin "1") (pinfunction "1_1") (pintype "passive"))
      (node (ref "C31") (pin "1") (pinfunction "1_1") (pintype "passive"))
      (node (ref "C73") (pin "1") (pinfunction "1_1") (pintype "passive"))
      (node (ref "C74") (pin "1") (pinfunction "1_1") (pintype "passive"))
      (node (ref "C75") (pin "1") (pinfunction "1_1") (pintype "passive"))
      (node (ref "C85") (pin "1") (pinfunction "1_1") (pintype "passive"))
      (node (ref "C86") (pin "1") (pinfunction "1_1") (pintype "passive"))
      (node (ref "C88") (pin "1") (pinfunction "1_1") (pintype "passive"))
      (node (ref "C89") (pin "1") (pinfunction "1_1") (pintype "passive"))
      (node (ref "J8") (pin "10") (pinfunction "MH1_10") (pintype "passive"))
      (node (ref "J8") (pin "11") (pinfunction "MH2_11") (pintype "passive"))
      (node (ref "J8") (pin "3") (pinfunction "3_3") (pintype "passive"))
      (node (ref "J9") (pin "10") (pinfunction "MH1_10") (pintype "passive"))
      (node (ref "J9") (pin "11") (pinfunction "MH2_11") (pintype "passive"))
      (node (ref "J9") (pin "3") (pinfunction "3_3") (pintype "passive"))
      (node (ref "P4") (pin "28") (pinfunction "28_28") (pintype "passive"))
      (node (ref "P4") (pin "29") (pinfunction "29_29") (pintype "passive"))
      (node (ref "P4") (pin "30") (pinfunction "30_30") (pintype "passive"))
      (node (ref "P4") (pin "31") (pinfunction "31_31") (pintype "passive"))
      (node (ref "P4") (pin "32") (pinfunction "32_32") (pintype "passive"))
      (node (ref "P4") (pin "33") (pinfunction "33_33") (pintype "passive"))
      (node (ref "P4") (pin "34") (pinfunction "34_34") (pintype "passive"))
      (node (ref "P4") (pin "35") (pinfunction "35_35") (pintype "passive"))
      (node (ref "P4") (pin "36") (pinfunction "36_36") (pintype "passive"))
      (node (ref "P4") (pin "37") (pinfunction "37_37") (pintype "passive"))
      (node (ref "P4") (pin "38") (pinfunction "38_38") (pintype "passive"))
      (node (ref "P4") (pin "39") (pinfunction "39_39") (pintype "passive"))
      (node (ref "P4") (pin "40") (pinfunction "40_40") (pintype "passive"))
      (node (ref "P4") (pin "41") (pinfunction "41_41") (pintype "passive"))
      (node (ref "P4") (pin "42") (pinfunction "42_42") (pintype "passive"))
      (node (ref "P4") (pin "55") (pinfunction "55_55") (pintype "passive"))
      (node (ref "Q23") (pin "2") (pinfunction "2_2") (pintype "passive"))
      (node (ref "Q24") (pin "2") (pinfunction "2_2") (pintype "passive"))
      (node (ref "Q25") (pin "2") (pinfunction "2_2") (pintype "passive"))
      (node (ref "Q26") (pin "2") (pinfunction "2_2") (pintype "passive"))
      (node (ref "R12") (pin "2") (pintype "passive"))
      (node (ref "R135") (pin "1") (pintype "passive"))
      (node (ref "R136") (pin "1") (pintype "passive"))
      (node (ref "R137") (pin "1") (pintype "passive"))
      (node (ref "R138") (pin "1") (pintype "passive"))
      (node (ref "R167") (pin "2") (pintype "passive"))
      (node (ref "R50") (pin "2") (pintype "passive"))
      (node (ref "U10") (pin "6") (pinfunction "6_6") (pintype "passive"))
      (node (ref "U10") (pin "7") (pinfunction "7_7") (pintype "passive"))
      (node (ref "U28") (pin "2") (pinfunction "K_2") (pintype "passive"))
      (node (ref "U29") (pin "2") (pinfunction "K_2") (pintype "passive"))
      (node (ref "U34") (pin "5") (pinfunction "GND2_5") (pintype "passive"))
      (node (ref "U35") (pin "2") (pinfunction "VSS_2") (pintype "passive"))
      (node (ref "U51") (pin "5") (pinfunction "GND2_5") (pintype "passive"))
      (node (ref "U52") (pin "2") (pinfunction "VSS_2") (pintype "passive"))
      (node (ref "U53") (pin "6") (pinfunction "6_6") (pintype "passive"))
      (node (ref "U53") (pin "7") (pinfunction "7_7") (pintype "passive"))
      (node (ref "U54") (pin "6") (pinfunction "6_6") (pintype "passive"))
      (node (ref "U54") (pin "7") (pinfunction "7_7") (pintype "passive"))
      (node (ref "U57") (pin "4") (pinfunction "AGND_4") (pintype "passive"))
      (node (ref "U57") (pin "5") (pinfunction "SYNC_5") (pintype "passive"))
      (node (ref "U57") (pin "8") (pinfunction "PGND_8") (pintype "passive"))
      (node (ref "U7") (pin "6") (pinfunction "6_6") (pintype "passive"))
      (node (ref "U7") (pin "7") (pinfunction "7_7") (pintype "passive"))
    )
    (net (code "64") (name "Net-(D15-A)") (class "Default")
      (node (ref "D15") (pin "1") (pinfunction "A_1") (pintype "passive"))
      (node (ref "K1") (pin "2") (pinfunction "2_2") (pintype "passive"))
      (node (ref "Q23") (pin "3") (pinfunction "3_3") (pintype "passive"))
    )
    (net (code "65") (name "Net-(D16-A)") (class "Default")
      (node (ref "D16") (pin "1") (pinfunction "A_1") (pintype "passive"))
      (node (ref "K2") (pin "2") (pinfunction "2_2") (pintype "passive"))
      (node (ref "Q24") (pin "3") (pinfunction "3_3") (pintype "passive"))
    )
    (net (code "66") (name "Net-(D17-A)") (class "Default")
      (node (ref "D17") (pin "1") (pinfunction "A_1") (pintype "passive"))
      (node (ref "K3") (pin "2") (pinfunction "2_2") (pintype "passive"))
      (node (ref "Q25") (pin "3") (pinfunction "3_3") (pintype "passive"))
    )
    (net (code "67") (name "Net-(D18-A)") (class "Default")
      (node (ref "D18") (pin "1") (pinfunction "A_1") (pintype "passive"))
      (node (ref "K4") (pin "2") (pinfunction "2_2") (pintype "passive"))
      (node (ref "Q26") (pin "3") (pinfunction "3_3") (pintype "passive"))
    )
    (net (code "68") (name "Net-(LED7-Pad1)") (class "Default")
      (node (ref "LED7") (pin "1") (pinfunction "1_1") (pintype "passive"))
      (node (ref "Q28") (pin "3") (pinfunction "3_3") (pintype "passive"))
    )
    (net (code "69") (name "Net-(LED8-Pad1)") (class "Default")
      (node (ref "LED8") (pin "1") (pinfunction "1_1") (pintype "passive"))
      (node (ref "Q27") (pin "3") (pinfunction "3_3") (pintype "passive"))
    )
    (net (code "70") (name "Net-(LED9-Pad1)") (class "Default")
      (node (ref "LED9") (pin "1") (pinfunction "1_1") (pintype "passive"))
      (node (ref "Q29") (pin "3") (pinfunction "3_3") (pintype "passive"))
    )
    (net (code "71") (name "Net-(LED10-Pad1)") (class "Default")
      (node (ref "LED10") (pin "1") (pinfunction "1_1") (pintype "passive"))
      (node (ref "Q30") (pin "3") (pinfunction "3_3") (pintype "passive"))
    )
    (net (code "72") (name "Net-(Q27-Pad1)") (class "Default")
      (node (ref "Q27") (pin "1") (pinfunction "1_1") (pintype "passive"))
      (node (ref "R131") (pin "1") (pintype "passive"))
    )
    (net (code "73") (name "Net-(Q27-Pad2)") (class "Default")
      (node (ref "Q27") (pin "2") (pinfunction "2_2") (pintype "passive"))
      (node (ref "R135") (pin "2") (pintype "passive"))
    )
    (net (code "74") (name "Net-(Q28-Pad1)") (class "Default")
      (node (ref "Q28") (pin "1") (pinfunction "1_1") (pintype "passive"))
      (node (ref "R132") (pin "1") (pintype "passive"))
    )
    (net (code "75") (name "Net-(Q28-Pad2)") (class "Default")
      (node (ref "Q28") (pin "2") (pinfunction "2_2") (pintype "passive"))
      (node (ref "R136") (pin "2") (pintype "passive"))
    )
    (net (code "76") (name "Net-(Q29-Pad1)") (class "Default")
      (node (ref "Q29") (pin "1") (pinfunction "1_1") (pintype "passive"))
      (node (ref "R133") (pin "1") (pintype "passive"))
    )
    (net (code "77") (name "Net-(Q29-Pad2)") (class "Default")
      (node (ref "Q29") (pin "2") (pinfunction "2_2") (pintype "passive"))
      (node (ref "R137") (pin "2") (pintype "passive"))
    )
    (net (code "78") (name "Net-(Q30-Pad1)") (class "Default")
      (node (ref "Q30") (pin "1") (pinfunction "1_1") (pintype "passive"))
      (node (ref "R134") (pin "1") (pintype "passive"))
    )
    (net (code "79") (name "Net-(Q30-Pad2)") (class "Default")
      (node (ref "Q30") (pin "2") (pinfunction "2_2") (pintype "passive"))
      (node (ref "R138") (pin "2") (pintype "passive"))
    )
    (net (code "80") (name "Net-(U26-A)") (class "Default")
      (node (ref "R87") (pin "2") (pintype "passive"))
      (node (ref "U26") (pin "1") (pinfunction "A_1") (pintype "passive"))
    )
    (net (code "81") (name "Net-(U26-C)") (class "Default")
      (node (ref "R106") (pin "1") (pintype "passive"))
      (node (ref "U26") (pin "4") (pinfunction "C_4") (pintype "passive"))
    )
    (net (code "82") (name "Net-(U27-A)") (class "Default")
      (node (ref "R88") (pin "2") (pintype "passive"))
      (node (ref "U27") (pin "1") (pinfunction "A_1") (pintype "passive"))
    )
    (net (code "83") (name "Net-(U27-C)") (class "Default")
      (node (ref "R107") (pin "1") (pintype "passive"))
      (node (ref "U27") (pin "4") (pinfunction "C_4") (pintype "passive"))
    )
    (net (code "84") (name "Net-(U28-A)") (class "Default")
      (node (ref "R108") (pin "2") (pintype "passive"))
      (node (ref "U28") (pin "1") (pinfunction "A_1") (pintype "passive"))
    )
    (net (code "85") (name "Net-(U29-A)") (class "Default")
      (node (ref "R109") (pin "2") (pintype "passive"))
      (node (ref "U29") (pin "1") (pinfunction "A_1") (pintype "passive"))
    )
    (net (code "86") (name "Net-(U30-A)") (class "Default")
      (node (ref "R91") (pin "2") (pintype "passive"))
      (node (ref "U30") (pin "1") (pinfunction "A_1") (pintype "passive"))
    )
    (net (code "87") (name "Net-(U30-C)") (class "Default")
      (node (ref "R110") (pin "1") (pintype "passive"))
      (node (ref "U30") (pin "4") (pinfunction "C_4") (pintype "passive"))
    )
    (net (code "88") (name "Net-(U31-A)") (class "Default")
      (node (ref "R92") (pin "2") (pintype "passive"))
      (node (ref "U31") (pin "1") (pinfunction "A_1") (pintype "passive"))
    )
    (net (code "89") (name "Net-(U31-C)") (class "Default")
      (node (ref "R111") (pin "1") (pintype "passive"))
      (node (ref "U31") (pin "4") (pinfunction "C_4") (pintype "passive"))
    )
    (net (code "90") (name "Net-(U32-A)") (class "Default")
      (node (ref "R93") (pin "2") (pintype "passive"))
      (node (ref "U32") (pin "1") (pinfunction "A_1") (pintype "passive"))
    )
    (net (code "91") (name "Net-(U32-C)") (class "Default")
      (node (ref "R112") (pin "1") (pintype "passive"))
      (node (ref "U32") (pin "4") (pinfunction "C_4") (pintype "passive"))
    )
    (net (code "92") (name "Net-(U33-A)") (class "Default")
      (node (ref "R94") (pin "2") (pintype "passive"))
      (node (ref "U33") (pin "1") (pinfunction "A_1") (pintype "passive"))
    )
    (net (code "93") (name "Net-(U33-C)") (class "Default")
      (node (ref "R113") (pin "1") (pintype "passive"))
      (node (ref "U33") (pin "4") (pinfunction "C_4") (pintype "passive"))
    )
    (net (code "94") (name "Net-(U35-RS)") (class "Default")
      (node (ref "R50") (pin "1") (pintype "passive"))
      (node (ref "U35") (pin "8") (pinfunction "RS_8") (pintype "passive"))
    )
    (net (code "95") (name "Net-(U52-RS)") (class "Default")
      (node (ref "R12") (pin "1") (pintype "passive"))
      (node (ref "U52") (pin "8") (pinfunction "RS_8") (pintype "passive"))
    )
    (net (code "96") (name "Net-(U57-SW)") (class "Default")
      (node (ref "L2") (pin "2") (pintype "passive"))
      (node (ref "U57") (pin "7") (pinfunction "SW_7") (pintype "passive"))
    )
    (net (code "97") (name "Net-(U57-VFB)") (class "Default")
      (node (ref "C87") (pin "1") (pinfunction "1_1") (pintype "passive"))
      (node (ref "R166") (pin "2") (pintype "passive"))
      (node (ref "R167") (pin "1") (pintype "passive"))
      (node (ref "U57") (pin "3") (pinfunction "VFB_3") (pintype "passive"))
    )
    (net (code "98") (name "VCC") (class "Default")
      (node (ref "C27") (pin "2") (pinfunction "2_2") (pintype "passive"))
      (node (ref "C72") (pin "2") (pinfunction "2_2") (pintype "passive"))
      (node (ref "R89") (pin "2") (pintype "passive"))
      (node (ref "R90") (pin "2") (pintype "passive"))
      (node (ref "U34") (pin "1") (pinfunction "VDD1_1") (pintype "passive"))
      (node (ref "U51") (pin "1") (pinfunction "VDD1_1") (pintype "passive"))
    )
    (net (code "99") (name "unconnected-(J8-Pad6)") (class "Default")
      (node (ref "J8") (pin "6") (pinfunction "6_6") (pintype "passive+no_connect"))
    )
    (net (code "100") (name "unconnected-(J8-Pad8)") (class "Default")
      (node (ref "J8") (pin "8") (pinfunction "8_8") (pintype "passive+no_connect"))
    )
    (net (code "101") (name "unconnected-(J9-Pad6)") (class "Default")
      (node (ref "J9") (pin "6") (pinfunction "6_6") (pintype "passive+no_connect"))
    )
    (net (code "102") (name "unconnected-(J9-Pad8)") (class "Default")
      (node (ref "J9") (pin "8") (pinfunction "8_8") (pintype "passive+no_connect"))
    )
    (net (code "103") (name "unconnected-(K1-Pad3)") (class "Default")
      (node (ref "K1") (pin "3") (pinfunction "3_3") (pintype "passive"))
    )
    (net (code "104") (name "unconnected-(K2-Pad3)") (class "Default")
      (node (ref "K2") (pin "3") (pinfunction "3_3") (pintype "passive"))
    )
    (net (code "105") (name "unconnected-(K3-Pad3)") (class "Default")
      (node (ref "K3") (pin "3") (pinfunction "3_3") (pintype "passive"))
    )
    (net (code "106") (name "unconnected-(K4-Pad3)") (class "Default")
      (node (ref "K4") (pin "3") (pinfunction "3_3") (pintype "passive"))
    )
    (net (code "107") (name "unconnected-(U7-Pad5)") (class "Default")
      (node (ref "U7") (pin "5") (pinfunction "5_5") (pintype "passive+no_connect"))
    )
    (net (code "108") (name "unconnected-(U7-Pad8)") (class "Default")
      (node (ref "U7") (pin "8") (pinfunction "8_8") (pintype "passive+no_connect"))
    )
    (net (code "109") (name "unconnected-(U10-Pad4)") (class "Default")
      (node (ref "U10") (pin "4") (pinfunction "4_4") (pintype "passive+no_connect"))
    )
    (net (code "110") (name "unconnected-(U10-Pad5)") (class "Default")
      (node (ref "U10") (pin "5") (pinfunction "5_5") (pintype "passive+no_connect"))
    )
    (net (code "111") (name "unconnected-(U35-VREF-Pad5)") (class "Default")
      (node (ref "U35") (pin "5") (pinfunction "VREF_5") (pintype "passive+no_connect"))
    )
    (net (code "112") (name "unconnected-(U52-VREF-Pad5)") (class "Default")
      (node (ref "U52") (pin "5") (pinfunction "VREF_5") (pintype "passive+no_connect"))
    )
    (net (code "113") (name "unconnected-(U54-Pad5)") (class "Default")
      (node (ref "U54") (pin "5") (pinfunction "5_5") (pintype "passive+no_connect"))
    )
    (net (code "114") (name "unconnected-(U54-Pad8)") (class "Default")
      (node (ref "U54") (pin "8") (pinfunction "8_8") (pintype "passive+no_connect"))
    )
  )
)
